# Connectors.net
KiCad netlist of a schematic drawn in Altium Designer
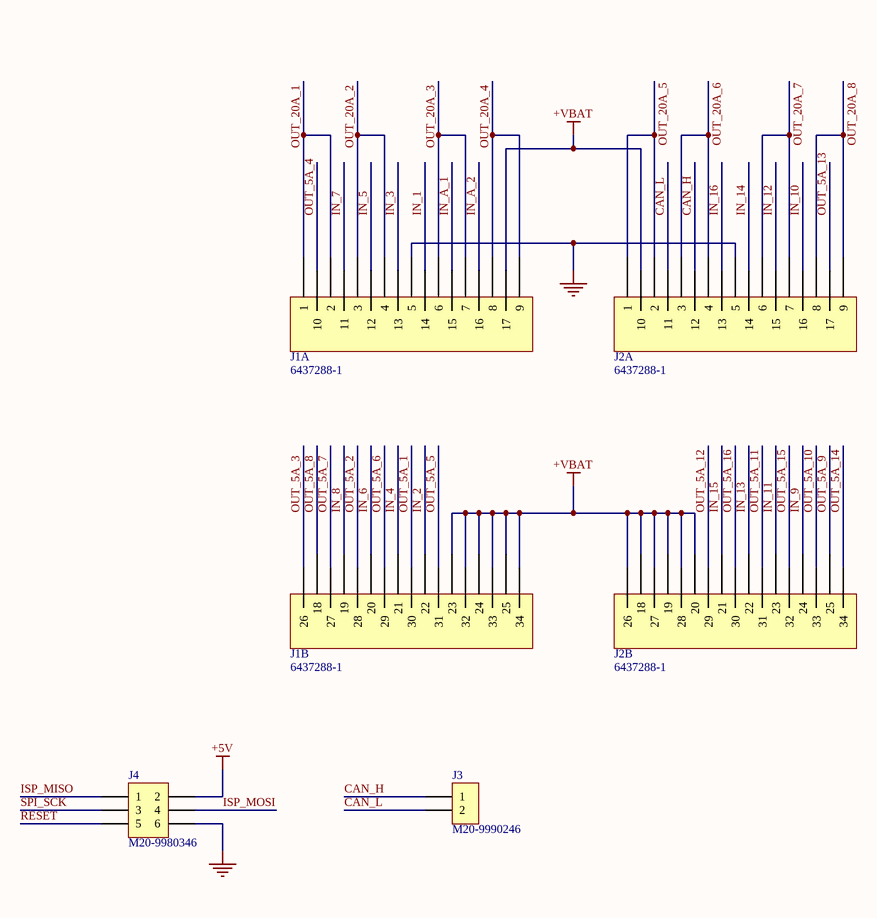
[diagram p0: Connectors.SchDoc]

(export (version "E")
  (design (tool "Eeschema 10.0.6"))
  (components
    (comp (ref "J1")
      (value "6437288-1")
      (footprint "6437288-1")
      (description "Superseal 34-way right angle PCB header")
      (libsource (lib "Connectors") (part "6437288-1"))
    )
    (comp (ref "J2")
      (value "6437288-1")
      (footprint "6437288-1")
      (description "Superseal 34-way right angle PCB header")
      (libsource (lib "Connectors") (part "6437288-1"))
    )
    (comp (ref "J3")
      (value "M20-9990246")
      (footprint "M20-9990246")
      (description "2.54mm Header 1x2-Pin")
      (libsource (lib "PDU-UV17") (part "M20-9990246"))
    )
    (comp (ref "J4")
      (value "M20-9980346")
      (footprint "M20-9980346")
      (description "2.54mm Header 2x3-Pin")
      (libsource (lib "PDU-UV17") (part "M20-9980346"))
    )
  )
  (nets
    (net (code "1") (name "+5V") (class "Default")
      (node (ref "J4") (pin "2") (pinfunction "2_2") (pintype "passive"))
    )
    (net (code "2") (name "+VBAT") (class "Default")
      (node (ref "J1") (pin "17") (pinfunction "17_17") (pintype "passive"))
      (node (ref "J1") (pin "23") (pinfunction "23_23") (pintype "passive"))
      (node (ref "J1") (pin "24") (pinfunction "24_24") (pintype "passive"))
      (node (ref "J1") (pin "25") (pinfunction "25_25") (pintype "passive"))
      (node (ref "J1") (pin "32") (pinfunction "32_32") (pintype "passive"))
      (node (ref "J1") (pin "33") (pinfunction "33_33") (pintype "passive"))
      (node (ref "J1") (pin "34") (pinfunction "34_34") (pintype "passive"))
      (node (ref "J2") (pin "10") (pinfunction "10_10") (pintype "passive"))
      (node (ref "J2") (pin "18") (pinfunction "18_18") (pintype "passive"))
      (node (ref "J2") (pin "19") (pinfunction "19_19") (pintype "passive"))
      (node (ref "J2") (pin "20") (pinfunction "20_20") (pintype "passive"))
      (node (ref "J2") (pin "26") (pinfunction "26_26") (pintype "passive"))
      (node (ref "J2") (pin "27") (pinfunction "27_27") (pintype "passive"))
      (node (ref "J2") (pin "28") (pinfunction "28_28") (pintype "passive"))
    )
    (net (code "3") (name "/CAN_H") (class "Default")
      (node (ref "J2") (pin "12") (pinfunction "12_12") (pintype "passive"))
      (node (ref "J3") (pin "1") (pinfunction "1_1") (pintype "passive"))
    )
    (net (code "4") (name "/CAN_L") (class "Default")
      (node (ref "J2") (pin "11") (pinfunction "11_11") (pintype "passive"))
      (node (ref "J3") (pin "2") (pinfunction "2_2") (pintype "passive"))
    )
    (net (code "5") (name "/IN_1") (class "Default")
      (node (ref "J1") (pin "14") (pinfunction "14_14") (pintype "passive"))
    )
    (net (code "6") (name "/IN_2") (class "Default")
      (node (ref "J1") (pin "22") (pinfunction "22_22") (pintype "passive"))
    )
    (net (code "7") (name "/IN_3") (class "Default")
      (node (ref "J1") (pin "13") (pinfunction "13_13") (pintype "passive"))
    )
    (net (code "8") (name "/IN_4") (class "Default")
      (node (ref "J1") (pin "21") (pinfunction "21_21") (pintype "passive"))
    )
    (net (code "9") (name "/IN_5") (class "Default")
      (node (ref "J1") (pin "12") (pinfunction "12_12") (pintype "passive"))
    )
    (net (code "10") (name "/IN_6") (class "Default")
      (node (ref "J1") (pin "20") (pinfunction "20_20") (pintype "passive"))
    )
    (net (code "11") (name "/IN_7") (class "Default")
      (node (ref "J1") (pin "11") (pinfunction "11_11") (pintype "passive"))
    )
    (net (code "12") (name "/IN_8") (class "Default")
      (node (ref "J1") (pin "19") (pinfunction "19_19") (pintype "passive"))
    )
    (net (code "13") (name "/IN_9") (class "Default")
      (node (ref "J2") (pin "24") (pinfunction "24_24") (pintype "passive"))
    )
    (net (code "14") (name "/IN_10") (class "Default")
      (node (ref "J2") (pin "16") (pinfunction "16_16") (pintype "passive"))
    )
    (net (code "15") (name "/IN_11") (class "Default")
      (node (ref "J2") (pin "23") (pinfunction "23_23") (pintype "passive"))
    )
    (net (code "16") (name "/IN_12") (class "Default")
      (node (ref "J2") (pin "15") (pinfunction "15_15") (pintype "passive"))
    )
    (net (code "17") (name "/IN_13") (class "Default")
      (node (ref "J2") (pin "22") (pinfunction "22_22") (pintype "passive"))
    )
    (net (code "18") (name "/IN_14") (class "Default")
      (node (ref "J2") (pin "14") (pinfunction "14_14") (pintype "passive"))
    )
    (net (code "19") (name "/IN_15") (class "Default")
      (node (ref "J2") (pin "21") (pinfunction "21_21") (pintype "passive"))
    )
    (net (code "20") (name "/IN_16") (class "Default")
      (node (ref "J2") (pin "13") (pinfunction "13_13") (pintype "passive"))
    )
    (net (code "21") (name "/IN_A_1") (class "Default")
      (node (ref "J1") (pin "15") (pinfunction "15_15") (pintype "passive"))
    )
    (net (code "22") (name "/IN_A_2") (class "Default")
      (node (ref "J1") (pin "16") (pinfunction "16_16") (pintype "passive"))
    )
    (net (code "23") (name "/ISP_MISO") (class "Default")
      (node (ref "J4") (pin "1") (pinfunction "1_1") (pintype "passive"))
    )
    (net (code "24") (name "/ISP_MOSI") (class "Default")
      (node (ref "J4") (pin "4") (pinfunction "4_4") (pintype "passive"))
    )
    (net (code "25") (name "/OUT_5A_1") (class "Default")
      (node (ref "J1") (pin "30") (pinfunction "30_30") (pintype "passive"))
    )
    (net (code "26") (name "/OUT_5A_2") (class "Default")
      (node (ref "J1") (pin "28") (pinfunction "28_28") (pintype "passive"))
    )
    (net (code "27") (name "/OUT_5A_3") (class "Default")
      (node (ref "J1") (pin "26") (pinfunction "26_26") (pintype "passive"))
    )
    (net (code "28") (name "/OUT_5A_4") (class "Default")
      (node (ref "J1") (pin "10") (pinfunction "10_10") (pintype "passive"))
    )
    (net (code "29") (name "/OUT_5A_5") (class "Default")
      (node (ref "J1") (pin "31") (pinfunction "31_31") (pintype "passive"))
    )
    (net (code "30") (name "/OUT_5A_6") (class "Default")
      (node (ref "J1") (pin "29") (pinfunction "29_29") (pintype "passive"))
    )
    (net (code "31") (name "/OUT_5A_7") (class "Default")
      (node (ref "J1") (pin "27") (pinfunction "27_27") (pintype "passive"))
    )
    (net (code "32") (name "/OUT_5A_8") (class "Default")
      (node (ref "J1") (pin "18") (pinfunction "18_18") (pintype "passive"))
    )
    (net (code "33") (name "/OUT_5A_9") (class "Default")
      (node (ref "J2") (pin "25") (pinfunction "25_25") (pintype "passive"))
    )
    (net (code "34") (name "/OUT_5A_10") (class "Default")
      (node (ref "J2") (pin "33") (pinfunction "33_33") (pintype "passive"))
    )
    (net (code "35") (name "/OUT_5A_11") (class "Default")
      (node (ref "J2") (pin "31") (pinfunction "31_31") (pintype "passive"))
    )
    (net (code "36") (name "/OUT_5A_12") (class "Default")
      (node (ref "J2") (pin "29") (pinfunction "29_29") (pintype "passive"))
    )
    (net (code "37") (name "/OUT_5A_13") (class "Default")
      (node (ref "J2") (pin "17") (pinfunction "17_17") (pintype "passive"))
    )
    (net (code "38") (name "/OUT_5A_14") (class "Default")
      (node (ref "J2") (pin "34") (pinfunction "34_34") (pintype "passive"))
    )
    (net (code "39") (name "/OUT_5A_15") (class "Default")
      (node (ref "J2") (pin "32") (pinfunction "32_32") (pintype "passive"))
    )
    (net (code "40") (name "/OUT_5A_16") (class "Default")
      (node (ref "J2") (pin "30") (pinfunction "30_30") (pintype "passive"))
    )
    (net (code "41") (name "/OUT_20A_1") (class "Default")
      (node (ref "J1") (pin "1") (pinfunction "1_1") (pintype "passive"))
      (node (ref "J1") (pin "2") (pinfunction "2_2") (pintype "passive"))
    )
    (net (code "42") (name "/OUT_20A_2") (class "Default")
      (node (ref "J1") (pin "3") (pinfunction "3_3") (pintype "passive"))
      (node (ref "J1") (pin "4") (pinfunction "4_4") (pintype "passive"))
    )
    (net (code "43") (name "/OUT_20A_3") (class "Default")
      (node (ref "J1") (pin "6") (pinfunction "6_6") (pintype "passive"))
      (node (ref "J1") (pin "7") (pinfunction "7_7") (pintype "passive"))
    )
    (net (code "44") (name "/OUT_20A_4") (class "Default")
      (node (ref "J1") (pin "8") (pinfunction "8_8") (pintype "passive"))
      (node (ref "J1") (pin "9") (pinfunction "9_9") (pintype "passive"))
    )
    (net (code "45") (name "/OUT_20A_5") (class "Default")
      (node (ref "J2") (pin "1") (pinfunction "1_1") (pintype "passive"))
      (node (ref "J2") (pin "2") (pinfunction "2_2") (pintype "passive"))
    )
    (net (code "46") (name "/OUT_20A_6") (class "Default")
      (node (ref "J2") (pin "3") (pinfunction "3_3") (pintype "passive"))
      (node (ref "J2") (pin "4") (pinfunction "4_4") (pintype "passive"))
    )
    (net (code "47") (name "/OUT_20A_7") (class "Default")
      (node (ref "J2") (pin "6") (pinfunction "6_6") (pintype "passive"))
      (node (ref "J2") (pin "7") (pinfunction "7_7") (pintype "passive"))
    )
    (net (code "48") (name "/OUT_20A_8") (class "Default")
      (node (ref "J2") (pin "8") (pinfunction "8_8") (pintype "passive"))
      (node (ref "J2") (pin "9") (pinfunction "9_9") (pintype "passive"))
    )
    (net (code "49") (name "/SPI_SCK") (class "Default")
      (node (ref "J4") (pin "3") (pinfunction "3_3") (pintype "passive"))
    )
    (net (code "50") (name "/~{RESET}") (class "Default")
      (node (ref "J4") (pin "5") (pinfunction "5_5") (pintype "passive"))
    )
    (net (code "51") (name "GND") (class "Default")
      (node (ref "J1") (pin "5") (pinfunction "5_5") (pintype "passive"))
      (node (ref "J2") (pin "5") (pinfunction "5_5") (pintype "passive"))
      (node (ref "J4") (pin "6") (pinfunction "6_6") (pintype "passive"))
    )
  )
)
